# Keithley_2000_SCAN_Panasonic_V1_0.net
KiCad netlist of a schematic drawn in EasyEDA Pro
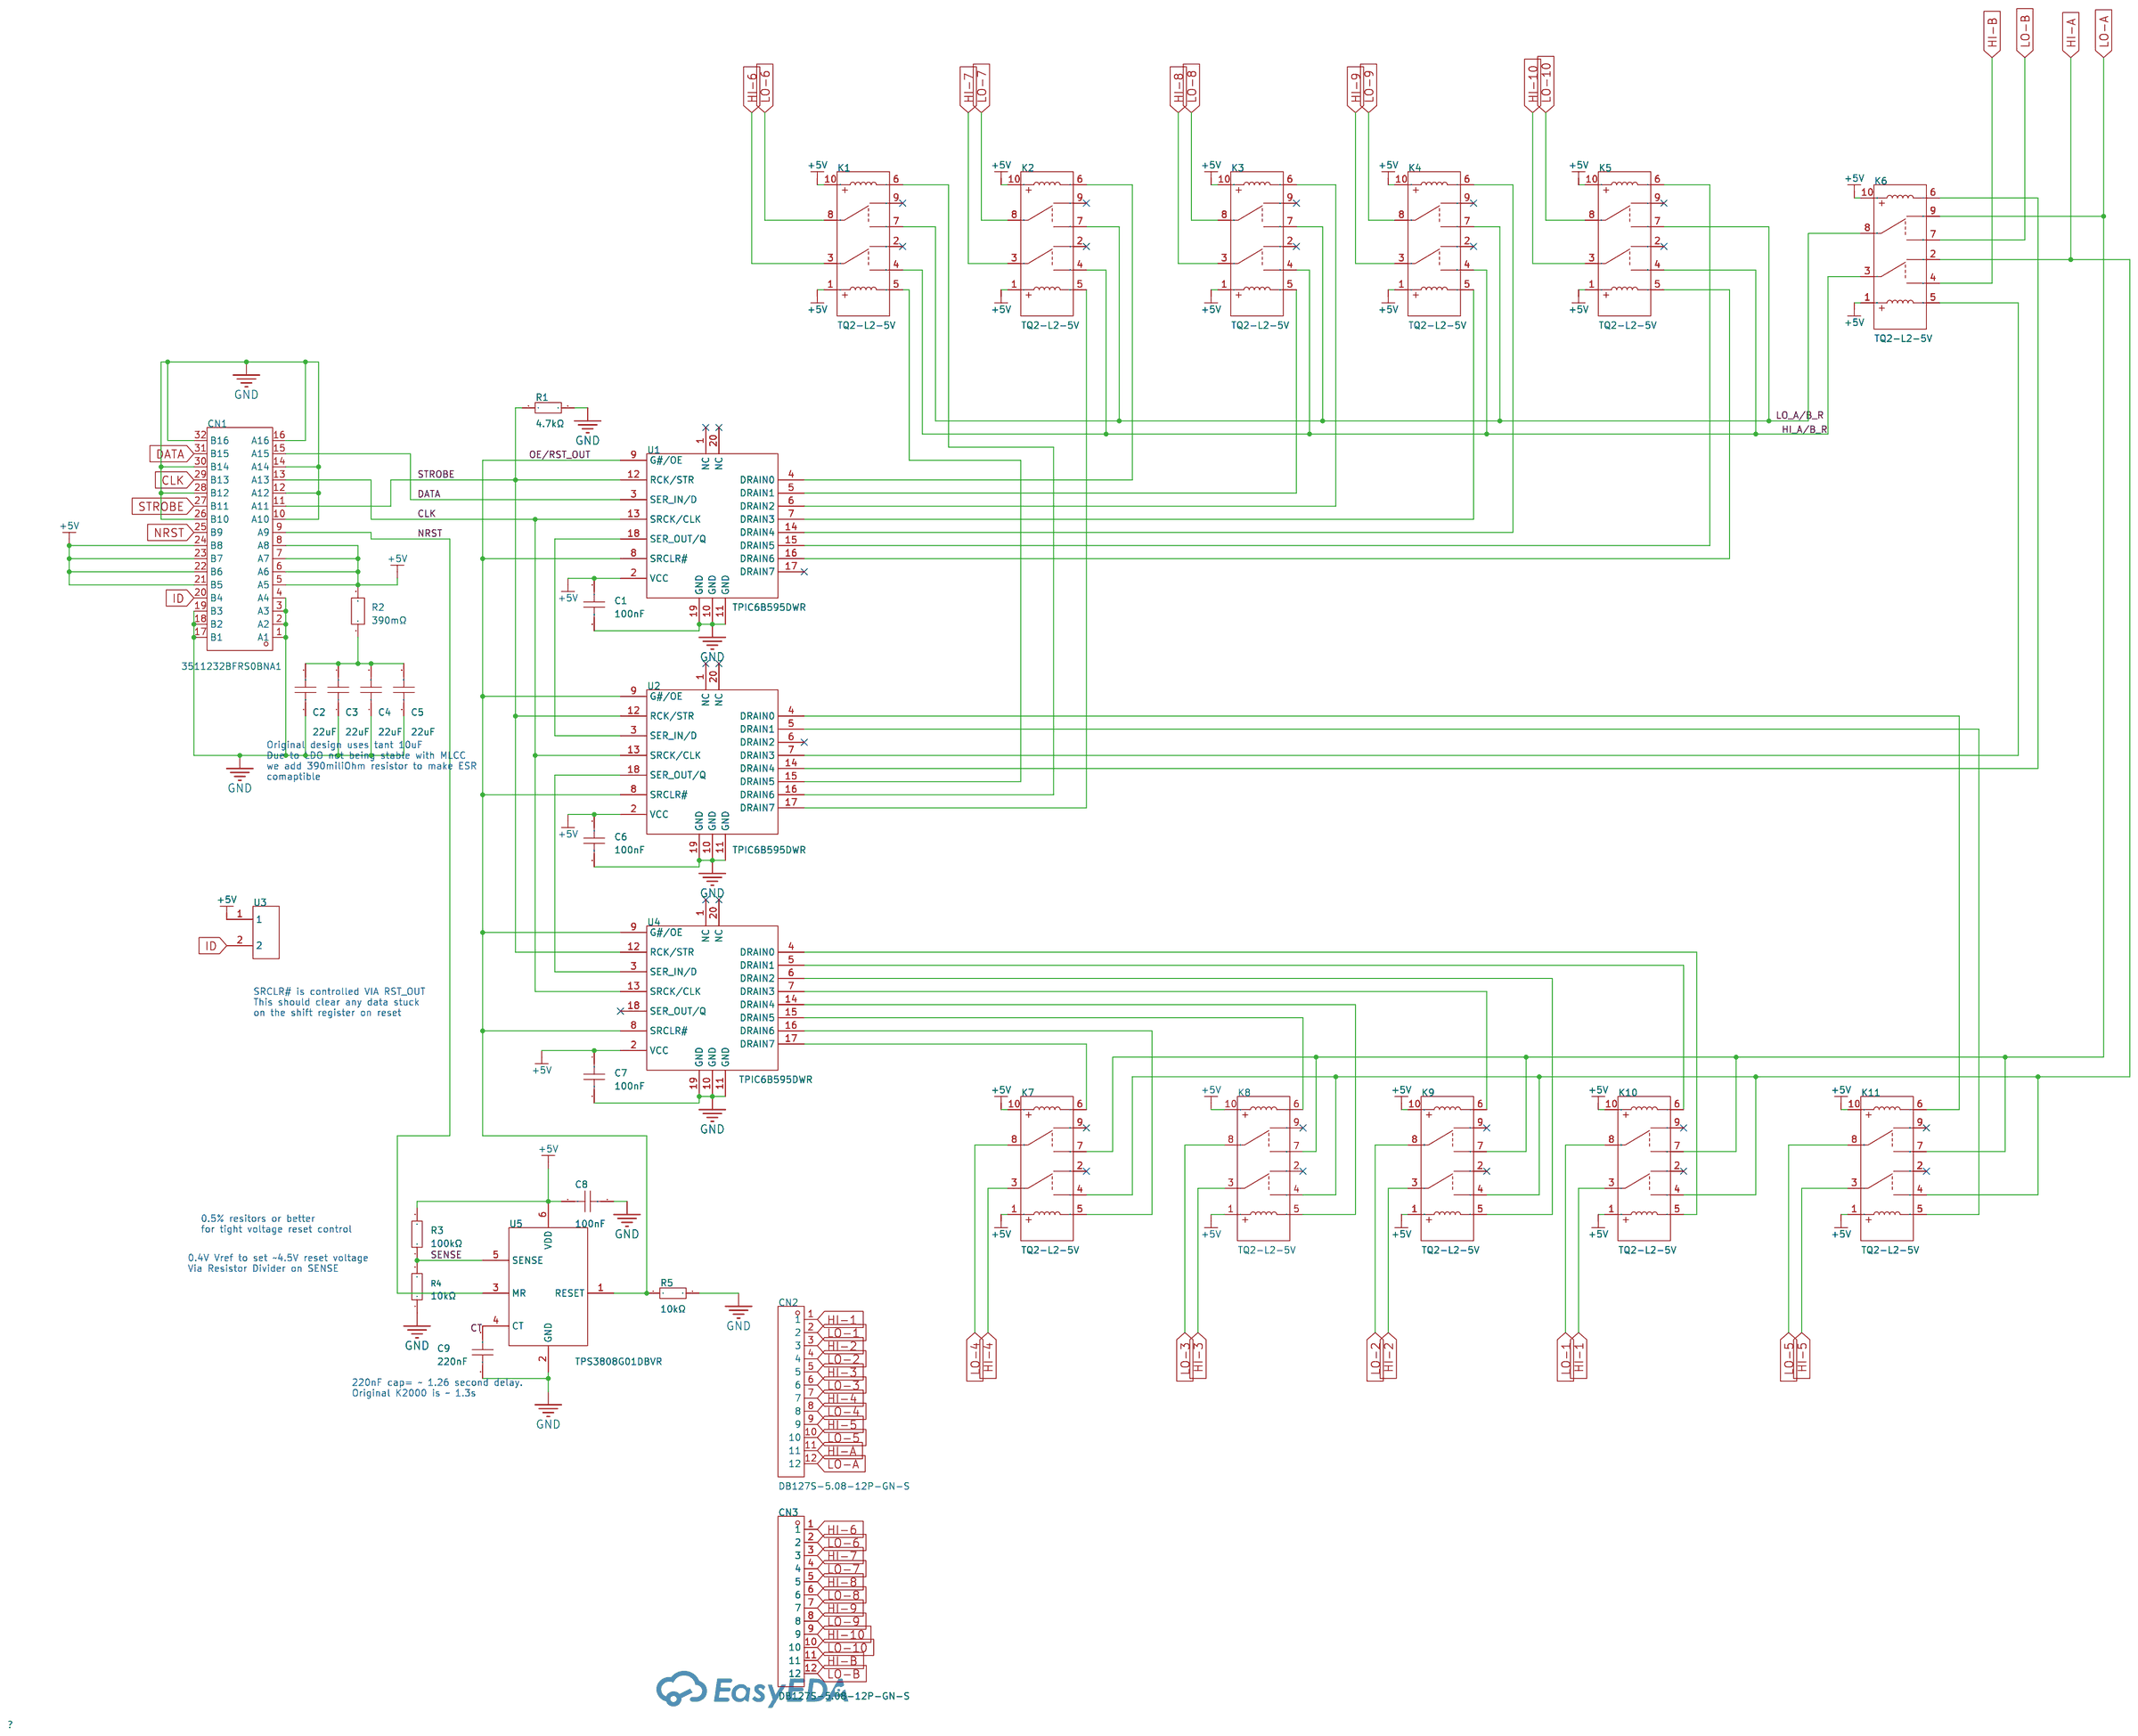
[diagram p0: schematic sheet]

(export (version "E")
  (design (tool "Eeschema 10.0.6"))
  (components
    (comp (ref "C1")
      (value "100nF")
      (description "Capacitance:100nF Tolerance:±10% Tolerance:±10% Voltage Rating:50V Temperature Coefficient:X7R")
      (fields
        (field (name "Manufacturer Part") "CL10B104KB8NNNC")
        (field (name "Manufacturer") "SAMSUNG(三星)")
      )
      (libsource (lib "easyedapro") (part "CAP"))
    )
    (comp (ref "C2")
      (value "22uF")
      (footprint "easyedapro:C0805")
      (description "Capacitance:22uF Tolerance:±20% Tolerance:±20% Voltage Rating:25V Temperature Coefficient:X5R")
      (fields
        (field (name "Manufacturer Part") "CL21A226MAYNNNE")
        (field (name "Manufacturer") "SAMSUNG(三星)")
      )
      (libsource (lib "easyedapro") (part "CL21A226MAYNNNE"))
    )
    (comp (ref "C3")
      (value "22uF")
      (footprint "easyedapro:C0805")
      (description "Capacitance:22uF Tolerance:±20% Tolerance:±20% Voltage Rating:25V Temperature Coefficient:X5R")
      (fields
        (field (name "Manufacturer Part") "CL21A226MAYNNNE")
        (field (name "Manufacturer") "SAMSUNG(三星)")
      )
      (libsource (lib "easyedapro") (part "CL21A226MAYNNNE"))
    )
    (comp (ref "C4")
      (value "22uF")
      (footprint "easyedapro:C0805")
      (description "Capacitance:22uF Tolerance:±20% Tolerance:±20% Voltage Rating:25V Temperature Coefficient:X5R")
      (fields
        (field (name "Manufacturer Part") "CL21A226MAYNNNE")
        (field (name "Manufacturer") "SAMSUNG(三星)")
      )
      (libsource (lib "easyedapro") (part "CL21A226MAYNNNE"))
    )
    (comp (ref "C5")
      (value "22uF")
      (footprint "easyedapro:C0805")
      (description "Capacitance:22uF Tolerance:±20% Tolerance:±20% Voltage Rating:25V Temperature Coefficient:X5R")
      (fields
        (field (name "Manufacturer Part") "CL21A226MAYNNNE")
        (field (name "Manufacturer") "SAMSUNG(三星)")
      )
      (libsource (lib "easyedapro") (part "CL21A226MAYNNNE"))
    )
    (comp (ref "C6")
      (value "100nF")
      (description "Capacitance:100nF Tolerance:±10% Tolerance:±10% Voltage Rating:50V Temperature Coefficient:X7R")
      (fields
        (field (name "Manufacturer Part") "CL10B104KB8NNNC")
        (field (name "Manufacturer") "SAMSUNG(三星)")
      )
      (libsource (lib "easyedapro") (part "CAP"))
    )
    (comp (ref "C7")
      (value "100nF")
      (description "Capacitance:100nF Tolerance:±10% Tolerance:±10% Voltage Rating:50V Temperature Coefficient:X7R")
      (fields
        (field (name "Manufacturer Part") "CL10B104KB8NNNC")
        (field (name "Manufacturer") "SAMSUNG(三星)")
      )
      (libsource (lib "easyedapro") (part "CAP"))
    )
    (comp (ref "C8")
      (value "100nF")
      (description "Capacitance:100nF Tolerance:±10% Tolerance:±10% Voltage Rating:50V Temperature Coefficient:X7R")
      (fields
        (field (name "Manufacturer Part") "CL10B104KB8NNNC")
        (field (name "Manufacturer") "SAMSUNG(三星)")
      )
      (libsource (lib "easyedapro") (part "CAP"))
    )
    (comp (ref "C9")
      (value "220nF")
      (description "Capacitance:220nF Tolerance:±10% Tolerance:±10% Voltage Rating:25V Temperature Coefficient:X7R")
      (fields
        (field (name "Manufacturer Part") "CL10B224KA8NNNC")
        (field (name "Manufacturer") "SAMSUNG(三星)")
      )
      (libsource (lib "easyedapro") (part "CAP"))
    )
    (comp (ref "CN1")
      (value "3511232BFRS0BNA1")
      (footprint "easyedapro:CONN-TH_3511232BFRS0BNA1")
      (fields (field (name "Manufacturer") "JILN(锦凌)"))
      (libsource (lib "easyedapro") (part "3511232BFRS0BNA1"))
    )
    (comp (ref "CN2")
      (value "DB127S-5.08-12P-GN-S")
      (footprint "easyedapro:CONN-TH_12P-P5.08_DB127S-5.08-12P-GN-S")
      (fields (field (name "Manufacturer") "DORABO(地博电气)"))
      (libsource (lib "easyedapro") (part "DB127S-5.08-12P-GN-S"))
    )
    (comp (ref "CN3")
      (value "DB127S-5.08-12P-GN-S")
      (footprint "easyedapro:CONN-TH_12P-P5.08_DB127S-5.08-12P-GN-S")
      (fields (field (name "Manufacturer") "DORABO(地博电气)"))
      (libsource (lib "easyedapro") (part "DB127S-5.08-12P-GN-S"))
    )
    (comp (ref "K1")
      (value "TQ2-L2-5V")
      (footprint "easyedapro:RELAY-TH_TQ2-L2-XXV")
      (fields (field (name "Manufacturer") "PANASONIC(松下)"))
      (libsource (lib "easyedapro") (part "TQ2-L2-5V"))
    )
    (comp (ref "K2")
      (value "TQ2-L2-5V")
      (footprint "easyedapro:RELAY-TH_TQ2-L2-XXV")
      (fields (field (name "Manufacturer") "PANASONIC(松下)"))
      (libsource (lib "easyedapro") (part "TQ2-L2-5V"))
    )
    (comp (ref "K3")
      (value "TQ2-L2-5V")
      (footprint "easyedapro:RELAY-TH_TQ2-L2-XXV")
      (fields (field (name "Manufacturer") "PANASONIC(松下)"))
      (libsource (lib "easyedapro") (part "TQ2-L2-5V"))
    )
    (comp (ref "K4")
      (value "TQ2-L2-5V")
      (footprint "easyedapro:RELAY-TH_TQ2-L2-XXV")
      (fields (field (name "Manufacturer") "PANASONIC(松下)"))
      (libsource (lib "easyedapro") (part "TQ2-L2-5V"))
    )
    (comp (ref "K5")
      (value "TQ2-L2-5V")
      (footprint "easyedapro:RELAY-TH_TQ2-L2-XXV")
      (fields (field (name "Manufacturer") "PANASONIC(松下)"))
      (libsource (lib "easyedapro") (part "TQ2-L2-5V"))
    )
    (comp (ref "K6")
      (value "TQ2-L2-5V")
      (footprint "easyedapro:RELAY-TH_TQ2-L2-XXV")
      (fields (field (name "Manufacturer") "PANASONIC(松下)"))
      (libsource (lib "easyedapro") (part "TQ2-L2-5V"))
    )
    (comp (ref "K7")
      (value "TQ2-L2-5V")
      (footprint "easyedapro:RELAY-TH_TQ2-L2-XXV")
      (fields (field (name "Manufacturer") "PANASONIC(松下)"))
      (libsource (lib "easyedapro") (part "TQ2-L2-5V"))
    )
    (comp (ref "K8")
      (value "TQ2-L2-5V")
      (footprint "easyedapro:RELAY-TH_TQ2-L2-XXV")
      (fields (field (name "Manufacturer") "PANASONIC(松下)"))
      (libsource (lib "easyedapro") (part "TQ2-L2-5V"))
    )
    (comp (ref "K9")
      (value "TQ2-L2-5V")
      (footprint "easyedapro:RELAY-TH_TQ2-L2-XXV")
      (fields (field (name "Manufacturer") "PANASONIC(松下)"))
      (libsource (lib "easyedapro") (part "TQ2-L2-5V"))
    )
    (comp (ref "K10")
      (value "TQ2-L2-5V")
      (footprint "easyedapro:RELAY-TH_TQ2-L2-XXV")
      (fields (field (name "Manufacturer") "PANASONIC(松下)"))
      (libsource (lib "easyedapro") (part "TQ2-L2-5V"))
    )
    (comp (ref "K11")
      (value "TQ2-L2-5V")
      (footprint "easyedapro:RELAY-TH_TQ2-L2-XXV")
      (fields (field (name "Manufacturer") "PANASONIC(松下)"))
      (libsource (lib "easyedapro") (part "TQ2-L2-5V"))
    )
    (comp (ref "R1")
      (value "4.7kΩ")
      (fields (field (name "Manufacturer Part") "RC0603FR-074K7L") (field (name "Manufacturer") "YAGEO(国巨)"))
      (libsource (lib "easyedapro") (part "Res"))
    )
    (comp (ref "R2")
      (value "390mΩ")
      (footprint "easyedapro:R1206")
      (fields (field (name "Manufacturer Part") "FRL1206FR390TS") (field (name "Manufacturer") "FOJAN(富捷)"))
      (libsource (lib "easyedapro") (part "FRL1206FR390TS"))
    )
    (comp (ref "R3")
      (value "100kΩ")
      (footprint "easyedapro:R0603")
      (fields (field (name "Manufacturer Part") "AR03DTCX1003") (field (name "Manufacturer") "Viking(光颉)"))
      (libsource (lib "easyedapro") (part "AR03DTCX1003"))
    )
    (comp (ref "R4")
      (value "10kΩ")
      (footprint "easyedapro:R0603")
      (fields
        (field (name "Manufacturer Part") "0603WAD1002T5E")
        (field (name "Manufacturer") "UNI-ROYAL(厚声)")
      )
      (libsource (lib "easyedapro") (part "0603WAD1002T5E"))
    )
    (comp (ref "R5")
      (value "10kΩ")
      (fields (field (name "Manufacturer Part") "RC0603FR-0710KL") (field (name "Manufacturer") "YAGEO(国巨)"))
      (libsource (lib "easyedapro") (part "Res"))
    )
    (comp (ref "U1")
      (value "TPIC6B595DWR")
      (footprint "easyedapro:SOIC-20_L13.0-W7.6-P1.27-LS10.3-BL")
      (fields (field (name "Manufacturer") "TI(德州仪器)"))
      (libsource (lib "easyedapro") (part "TPIC6B595DWR"))
    )
    (comp (ref "U2")
      (value "TPIC6B595DWR")
      (footprint "easyedapro:SOIC-20_L13.0-W7.6-P1.27-LS10.3-BL")
      (fields (field (name "Manufacturer") "TI(德州仪器)"))
      (libsource (lib "easyedapro") (part "TPIC6B595DWR"))
    )
    (comp (ref "U3")
      (value "~")
      (footprint "easyedapro:Solder Jumper New")
      (libsource (lib "easyedapro") (part "Solder Jumper New"))
    )
    (comp (ref "U4")
      (value "TPIC6B595DWR")
      (footprint "easyedapro:SOIC-20_L13.0-W7.6-P1.27-LS10.3-BL")
      (fields (field (name "Manufacturer") "TI(德州仪器)"))
      (libsource (lib "easyedapro") (part "TPIC6B595DWR"))
    )
    (comp (ref "U5")
      (value "TPS3808G01DBVR")
      (footprint "easyedapro:SOT-23-6_L2.9-W1.6-P0.95-LS2.8-BR")
      (fields (field (name "Manufacturer") "TI(德州仪器)"))
      (libsource (lib "easyedapro") (part "TPS3808G01DBVR"))
    )
  )
  (nets
    (net (code "1") (name "+5V") (class "Default")
      (node (ref "C1") (pin "1") (pinfunction "1_1") (pintype "input"))
      (node (ref "C6") (pin "1") (pinfunction "1_1") (pintype "input"))
      (node (ref "C7") (pin "1") (pinfunction "1_1") (pintype "input"))
      (node (ref "C8") (pin "2") (pinfunction "2_2") (pintype "input"))
      (node (ref "CN1") (pin "21") (pinfunction "B5_21") (pintype "unspecified"))
      (node (ref "CN1") (pin "22") (pinfunction "B6_22") (pintype "unspecified"))
      (node (ref "CN1") (pin "23") (pinfunction "B7_23") (pintype "unspecified"))
      (node (ref "CN1") (pin "24") (pinfunction "B8_24") (pintype "unspecified"))
      (node (ref "CN1") (pin "5") (pinfunction "A5_5") (pintype "unspecified"))
      (node (ref "CN1") (pin "6") (pinfunction "A6_6") (pintype "unspecified"))
      (node (ref "CN1") (pin "7") (pinfunction "A7_7") (pintype "unspecified"))
      (node (ref "CN1") (pin "8") (pinfunction "A8_8") (pintype "unspecified"))
      (node (ref "K1") (pin "1") (pinfunction "1_1") (pintype "unspecified"))
      (node (ref "K1") (pin "10") (pinfunction "6_10") (pintype "unspecified"))
      (node (ref "K10") (pin "1") (pinfunction "1_1") (pintype "unspecified"))
      (node (ref "K10") (pin "10") (pinfunction "6_10") (pintype "unspecified"))
      (node (ref "K11") (pin "1") (pinfunction "1_1") (pintype "unspecified"))
      (node (ref "K11") (pin "10") (pinfunction "6_10") (pintype "unspecified"))
      (node (ref "K2") (pin "1") (pinfunction "1_1") (pintype "unspecified"))
      (node (ref "K2") (pin "10") (pinfunction "6_10") (pintype "unspecified"))
      (node (ref "K3") (pin "1") (pinfunction "1_1") (pintype "unspecified"))
      (node (ref "K3") (pin "10") (pinfunction "6_10") (pintype "unspecified"))
      (node (ref "K4") (pin "1") (pinfunction "1_1") (pintype "unspecified"))
      (node (ref "K4") (pin "10") (pinfunction "6_10") (pintype "unspecified"))
      (node (ref "K5") (pin "1") (pinfunction "1_1") (pintype "unspecified"))
      (node (ref "K5") (pin "10") (pinfunction "6_10") (pintype "unspecified"))
      (node (ref "K6") (pin "1") (pinfunction "1_1") (pintype "unspecified"))
      (node (ref "K6") (pin "10") (pinfunction "6_10") (pintype "unspecified"))
      (node (ref "K7") (pin "1") (pinfunction "1_1") (pintype "unspecified"))
      (node (ref "K7") (pin "10") (pinfunction "6_10") (pintype "unspecified"))
      (node (ref "K8") (pin "1") (pinfunction "1_1") (pintype "unspecified"))
      (node (ref "K8") (pin "10") (pinfunction "6_10") (pintype "unspecified"))
      (node (ref "K9") (pin "1") (pinfunction "1_1") (pintype "unspecified"))
      (node (ref "K9") (pin "10") (pinfunction "6_10") (pintype "unspecified"))
      (node (ref "R2") (pin "2") (pinfunction "2_2") (pintype "unspecified"))
      (node (ref "R3") (pin "2") (pinfunction "2_2") (pintype "unspecified"))
      (node (ref "U1") (pin "2") (pinfunction "VCC_2") (pintype "unspecified"))
      (node (ref "U2") (pin "2") (pinfunction "VCC_2") (pintype "unspecified"))
      (node (ref "U3") (pin "1") (pinfunction "1_1") (pintype "input"))
      (node (ref "U4") (pin "2") (pinfunction "VCC_2") (pintype "unspecified"))
      (node (ref "U5") (pin "6") (pinfunction "VDD_6") (pintype "unspecified"))
    )
    (net (code "2") (name "/CT") (class "Default")
      (node (ref "C9") (pin "1") (pinfunction "1_1") (pintype "input"))
      (node (ref "U5") (pin "4") (pinfunction "CT_4") (pintype "unspecified"))
    )
    (net (code "3") (name "/HI_A{slash}B_R") (class "Default")
      (node (ref "K1") (pin "4") (pinfunction "5_4") (pintype "unspecified"))
      (node (ref "K2") (pin "4") (pinfunction "5_4") (pintype "unspecified"))
      (node (ref "K3") (pin "4") (pinfunction "5_4") (pintype "unspecified"))
      (node (ref "K4") (pin "4") (pinfunction "5_4") (pintype "unspecified"))
      (node (ref "K5") (pin "4") (pinfunction "5_4") (pintype "unspecified"))
      (node (ref "K6") (pin "3") (pinfunction "4_3") (pintype "unspecified"))
    )
    (net (code "4") (name "/LO_A{slash}B_R") (class "Default")
      (node (ref "K1") (pin "7") (pinfunction "8_7") (pintype "unspecified"))
      (node (ref "K2") (pin "7") (pinfunction "8_7") (pintype "unspecified"))
      (node (ref "K3") (pin "7") (pinfunction "8_7") (pintype "unspecified"))
      (node (ref "K4") (pin "7") (pinfunction "8_7") (pintype "unspecified"))
      (node (ref "K5") (pin "7") (pinfunction "8_7") (pintype "unspecified"))
      (node (ref "K6") (pin "8") (pinfunction "9_8") (pintype "unspecified"))
    )
    (net (code "5") (name "/OE{slash}RST_OUT") (class "Default")
      (node (ref "R5") (pin "1") (pinfunction "1_1") (pintype "input"))
      (node (ref "U1") (pin "8") (pinfunction "SRCLR#_8") (pintype "unspecified"))
      (node (ref "U1") (pin "9") (pinfunction "G#/OE_9") (pintype "unspecified"))
      (node (ref "U2") (pin "8") (pinfunction "SRCLR#_8") (pintype "unspecified"))
      (node (ref "U2") (pin "9") (pinfunction "G#/OE_9") (pintype "unspecified"))
      (node (ref "U4") (pin "8") (pinfunction "SRCLR#_8") (pintype "unspecified"))
      (node (ref "U4") (pin "9") (pinfunction "G#/OE_9") (pintype "unspecified"))
      (node (ref "U5") (pin "1") (pinfunction "RESET_1") (pintype "unspecified"))
    )
    (net (code "6") (name "/SENSE") (class "Default")
      (node (ref "R3") (pin "1") (pinfunction "1_1") (pintype "unspecified"))
      (node (ref "R4") (pin "2") (pinfunction "2_2") (pintype "input"))
      (node (ref "U5") (pin "5") (pinfunction "SENSE_5") (pintype "unspecified"))
    )
    (net (code "7") (name "CLK") (class "Default")
      (node (ref "CN1") (pin "13") (pinfunction "A13_13") (pintype "unspecified"))
      (node (ref "CN1") (pin "29") (pinfunction "B13_29") (pintype "unspecified"))
      (node (ref "U1") (pin "13") (pinfunction "SRCK/CLK_13") (pintype "unspecified"))
      (node (ref "U2") (pin "13") (pinfunction "SRCK/CLK_13") (pintype "unspecified"))
      (node (ref "U4") (pin "13") (pinfunction "SRCK/CLK_13") (pintype "unspecified"))
    )
    (net (code "8") (name "DATA") (class "Default")
      (node (ref "CN1") (pin "15") (pinfunction "A15_15") (pintype "unspecified"))
      (node (ref "CN1") (pin "31") (pinfunction "B15_31") (pintype "unspecified"))
      (node (ref "U1") (pin "3") (pinfunction "SER_IN/D_3") (pintype "unspecified"))
    )
    (net (code "9") (name "GND") (class "Default")
      (node (ref "C1") (pin "2") (pinfunction "2_2") (pintype "input"))
      (node (ref "C2") (pin "1") (pinfunction "1_1") (pintype "unspecified"))
      (node (ref "C3") (pin "1") (pinfunction "1_1") (pintype "unspecified"))
      (node (ref "C4") (pin "1") (pinfunction "1_1") (pintype "unspecified"))
      (node (ref "C5") (pin "1") (pinfunction "1_1") (pintype "unspecified"))
      (node (ref "C6") (pin "2") (pinfunction "2_2") (pintype "input"))
      (node (ref "C7") (pin "2") (pinfunction "2_2") (pintype "input"))
      (node (ref "C8") (pin "1") (pinfunction "1_1") (pintype "input"))
      (node (ref "C9") (pin "2") (pinfunction "2_2") (pintype "input"))
      (node (ref "CN1") (pin "1") (pinfunction "A1_1") (pintype "unspecified"))
      (node (ref "CN1") (pin "10") (pinfunction "A10_10") (pintype "unspecified"))
      (node (ref "CN1") (pin "12") (pinfunction "A12_12") (pintype "unspecified"))
      (node (ref "CN1") (pin "14") (pinfunction "A14_14") (pintype "unspecified"))
      (node (ref "CN1") (pin "16") (pinfunction "A16_16") (pintype "unspecified"))
      (node (ref "CN1") (pin "17") (pinfunction "B1_17") (pintype "unspecified"))
      (node (ref "CN1") (pin "18") (pinfunction "B2_18") (pintype "unspecified"))
      (node (ref "CN1") (pin "19") (pinfunction "B3_19") (pintype "unspecified"))
      (node (ref "CN1") (pin "2") (pinfunction "A2_2") (pintype "unspecified"))
      (node (ref "CN1") (pin "26") (pinfunction "B10_26") (pintype "unspecified"))
      (node (ref "CN1") (pin "28") (pinfunction "B12_28") (pintype "unspecified"))
      (node (ref "CN1") (pin "3") (pinfunction "A3_3") (pintype "unspecified"))
      (node (ref "CN1") (pin "30") (pinfunction "B14_30") (pintype "unspecified"))
      (node (ref "CN1") (pin "32") (pinfunction "B16_32") (pintype "unspecified"))
      (node (ref "CN1") (pin "4") (pinfunction "A4_4") (pintype "unspecified"))
      (node (ref "R1") (pin "2") (pinfunction "2_2") (pintype "input"))
      (node (ref "R4") (pin "1") (pinfunction "1_1") (pintype "input"))
      (node (ref "R5") (pin "2") (pinfunction "2_2") (pintype "input"))
      (node (ref "U1") (pin "10") (pinfunction "GND_10") (pintype "unspecified"))
      (node (ref "U1") (pin "11") (pinfunction "GND_11") (pintype "unspecified"))
      (node (ref "U1") (pin "19") (pinfunction "GND_19") (pintype "unspecified"))
      (node (ref "U2") (pin "10") (pinfunction "GND_10") (pintype "unspecified"))
      (node (ref "U2") (pin "11") (pinfunction "GND_11") (pintype "unspecified"))
      (node (ref "U2") (pin "19") (pinfunction "GND_19") (pintype "unspecified"))
      (node (ref "U4") (pin "10") (pinfunction "GND_10") (pintype "unspecified"))
      (node (ref "U4") (pin "11") (pinfunction "GND_11") (pintype "unspecified"))
      (node (ref "U4") (pin "19") (pinfunction "GND_19") (pintype "unspecified"))
      (node (ref "U5") (pin "2") (pinfunction "GND_2") (pintype "unspecified"))
    )
    (net (code "10") (name "HI-1") (class "Default")
      (node (ref "CN2") (pin "1") (pinfunction "1_1") (pintype "unspecified"))
      (node (ref "K10") (pin "3") (pinfunction "4_3") (pintype "unspecified"))
    )
    (net (code "11") (name "HI-2") (class "Default")
      (node (ref "CN2") (pin "3") (pinfunction "3_3") (pintype "unspecified"))
      (node (ref "K9") (pin "3") (pinfunction "4_3") (pintype "unspecified"))
    )
    (net (code "12") (name "HI-3") (class "Default")
      (node (ref "CN2") (pin "5") (pinfunction "5_5") (pintype "unspecified"))
      (node (ref "K8") (pin "3") (pinfunction "4_3") (pintype "unspecified"))
    )
    (net (code "13") (name "HI-4") (class "Default")
      (node (ref "CN2") (pin "7") (pinfunction "7_7") (pintype "unspecified"))
      (node (ref "K7") (pin "3") (pinfunction "4_3") (pintype "unspecified"))
    )
    (net (code "14") (name "HI-5") (class "Default")
      (node (ref "CN2") (pin "9") (pinfunction "9_9") (pintype "unspecified"))
      (node (ref "K11") (pin "3") (pinfunction "4_3") (pintype "unspecified"))
    )
    (net (code "15") (name "HI-6") (class "Default")
      (node (ref "CN3") (pin "1") (pinfunction "1_1") (pintype "unspecified"))
      (node (ref "K1") (pin "3") (pinfunction "4_3") (pintype "unspecified"))
    )
    (net (code "16") (name "HI-7") (class "Default")
      (node (ref "CN3") (pin "3") (pinfunction "3_3") (pintype "unspecified"))
      (node (ref "K2") (pin "3") (pinfunction "4_3") (pintype "unspecified"))
    )
    (net (code "17") (name "HI-8") (class "Default")
      (node (ref "CN3") (pin "5") (pinfunction "5_5") (pintype "unspecified"))
      (node (ref "K3") (pin "3") (pinfunction "4_3") (pintype "unspecified"))
    )
    (net (code "18") (name "HI-9") (class "Default")
      (node (ref "CN3") (pin "7") (pinfunction "7_7") (pintype "unspecified"))
      (node (ref "K4") (pin "3") (pinfunction "4_3") (pintype "unspecified"))
    )
    (net (code "19") (name "HI-10") (class "Default")
      (node (ref "CN3") (pin "9") (pinfunction "9_9") (pintype "unspecified"))
      (node (ref "K5") (pin "3") (pinfunction "4_3") (pintype "unspecified"))
    )
    (net (code "20") (name "HI-A") (class "Default")
      (node (ref "CN2") (pin "11") (pinfunction "11_11") (pintype "unspecified"))
      (node (ref "K10") (pin "4") (pinfunction "5_4") (pintype "unspecified"))
      (node (ref "K11") (pin "4") (pinfunction "5_4") (pintype "unspecified"))
      (node (ref "K6") (pin "2") (pinfunction "3_2") (pintype "unspecified"))
      (node (ref "K7") (pin "4") (pinfunction "5_4") (pintype "unspecified"))
      (node (ref "K8") (pin "4") (pinfunction "5_4") (pintype "unspecified"))
      (node (ref "K9") (pin "4") (pinfunction "5_4") (pintype "unspecified"))
    )
    (net (code "21") (name "HI-B") (class "Default")
      (node (ref "CN3") (pin "11") (pinfunction "11_11") (pintype "unspecified"))
      (node (ref "K6") (pin "4") (pinfunction "5_4") (pintype "unspecified"))
    )
    (net (code "22") (name "ID") (class "Default")
      (node (ref "CN1") (pin "20") (pinfunction "B4_20") (pintype "unspecified"))
      (node (ref "U3") (pin "2") (pinfunction "2_2") (pintype "input"))
    )
    (net (code "23") (name "LO-1") (class "Default")
      (node (ref "CN2") (pin "2") (pinfunction "2_2") (pintype "unspecified"))
      (node (ref "K10") (pin "8") (pinfunction "9_8") (pintype "unspecified"))
    )
    (net (code "24") (name "LO-2") (class "Default")
      (node (ref "CN2") (pin "4") (pinfunction "4_4") (pintype "unspecified"))
      (node (ref "K9") (pin "8") (pinfunction "9_8") (pintype "unspecified"))
    )
    (net (code "25") (name "LO-3") (class "Default")
      (node (ref "CN2") (pin "6") (pinfunction "6_6") (pintype "unspecified"))
      (node (ref "K8") (pin "8") (pinfunction "9_8") (pintype "unspecified"))
    )
    (net (code "26") (name "LO-4") (class "Default")
      (node (ref "CN2") (pin "8") (pinfunction "8_8") (pintype "unspecified"))
      (node (ref "K7") (pin "8") (pinfunction "9_8") (pintype "unspecified"))
    )
    (net (code "27") (name "LO-5") (class "Default")
      (node (ref "CN2") (pin "10") (pinfunction "10_10") (pintype "unspecified"))
      (node (ref "K11") (pin "8") (pinfunction "9_8") (pintype "unspecified"))
    )
    (net (code "28") (name "LO-6") (class "Default")
      (node (ref "CN3") (pin "2") (pinfunction "2_2") (pintype "unspecified"))
      (node (ref "K1") (pin "8") (pinfunction "9_8") (pintype "unspecified"))
    )
    (net (code "29") (name "LO-7") (class "Default")
      (node (ref "CN3") (pin "4") (pinfunction "4_4") (pintype "unspecified"))
      (node (ref "K2") (pin "8") (pinfunction "9_8") (pintype "unspecified"))
    )
    (net (code "30") (name "LO-8") (class "Default")
      (node (ref "CN3") (pin "6") (pinfunction "6_6") (pintype "unspecified"))
      (node (ref "K3") (pin "8") (pinfunction "9_8") (pintype "unspecified"))
    )
    (net (code "31") (name "LO-9") (class "Default")
      (node (ref "CN3") (pin "8") (pinfunction "8_8") (pintype "unspecified"))
      (node (ref "K4") (pin "8") (pinfunction "9_8") (pintype "unspecified"))
    )
    (net (code "32") (name "LO-10") (class "Default")
      (node (ref "CN3") (pin "10") (pinfunction "10_10") (pintype "unspecified"))
      (node (ref "K5") (pin "8") (pinfunction "9_8") (pintype "unspecified"))
    )
    (net (code "33") (name "LO-A") (class "Default")
      (node (ref "CN2") (pin "12") (pinfunction "12_12") (pintype "unspecified"))
      (node (ref "K10") (pin "7") (pinfunction "8_7") (pintype "unspecified"))
      (node (ref "K11") (pin "7") (pinfunction "8_7") (pintype "unspecified"))
      (node (ref "K6") (pin "9") (pinfunction "10_9") (pintype "unspecified"))
      (node (ref "K7") (pin "7") (pinfunction "8_7") (pintype "unspecified"))
      (node (ref "K8") (pin "7") (pinfunction "8_7") (pintype "unspecified"))
      (node (ref "K9") (pin "7") (pinfunction "8_7") (pintype "unspecified"))
    )
    (net (code "34") (name "LO-B") (class "Default")
      (node (ref "CN3") (pin "12") (pinfunction "12_12") (pintype "unspecified"))
      (node (ref "K6") (pin "7") (pinfunction "8_7") (pintype "unspecified"))
    )
    (net (code "35") (name "NRST") (class "Default")
      (node (ref "CN1") (pin "25") (pinfunction "B9_25") (pintype "unspecified"))
      (node (ref "CN1") (pin "9") (pinfunction "A9_9") (pintype "unspecified"))
      (node (ref "U5") (pin "3") (pinfunction "MR_3") (pintype "unspecified"))
    )
    (net (code "36") (name "Net-(C2-Pad2)") (class "Default")
      (node (ref "C2") (pin "2") (pinfunction "2_2") (pintype "unspecified"))
      (node (ref "C3") (pin "2") (pinfunction "2_2") (pintype "unspecified"))
      (node (ref "C4") (pin "2") (pinfunction "2_2") (pintype "unspecified"))
      (node (ref "C5") (pin "2") (pinfunction "2_2") (pintype "unspecified"))
      (node (ref "R2") (pin "1") (pinfunction "1_1") (pintype "unspecified"))
    )
    (net (code "37") (name "Net-(K1-7)") (class "Default")
      (node (ref "K1") (pin "6") (pinfunction "7_6") (pintype "unspecified"))
      (node (ref "U2") (pin "16") (pinfunction "DRAIN6_16") (pintype "unspecified"))
    )
    (net (code "38") (name "Net-(K1-12)") (class "Default")
      (node (ref "K1") (pin "5") (pinfunction "12_5") (pintype "unspecified"))
      (node (ref "U2") (pin "15") (pinfunction "DRAIN5_15") (pintype "unspecified"))
    )
    (net (code "39") (name "Net-(K2-7)") (class "Default")
      (node (ref "K2") (pin "6") (pinfunction "7_6") (pintype "unspecified"))
      (node (ref "U1") (pin "4") (pinfunction "DRAIN0_4") (pintype "unspecified"))
    )
    (net (code "40") (name "Net-(K2-12)") (class "Default")
      (node (ref "K2") (pin "5") (pinfunction "12_5") (pintype "unspecified"))
      (node (ref "U2") (pin "17") (pinfunction "DRAIN7_17") (pintype "unspecified"))
    )
    (net (code "41") (name "Net-(K3-7)") (class "Default")
      (node (ref "K3") (pin "6") (pinfunction "7_6") (pintype "unspecified"))
      (node (ref "U1") (pin "6") (pinfunction "DRAIN2_6") (pintype "unspecified"))
    )
    (net (code "42") (name "Net-(K3-12)") (class "Default")
      (node (ref "K3") (pin "5") (pinfunction "12_5") (pintype "unspecified"))
      (node (ref "U1") (pin "5") (pinfunction "DRAIN1_5") (pintype "unspecified"))
    )
    (net (code "43") (name "Net-(K4-7)") (class "Default")
      (node (ref "K4") (pin "6") (pinfunction "7_6") (pintype "unspecified"))
      (node (ref "U1") (pin "14") (pinfunction "DRAIN4_14") (pintype "unspecified"))
    )
    (net (code "44") (name "Net-(K4-12)") (class "Default")
      (node (ref "K4") (pin "5") (pinfunction "12_5") (pintype "unspecified"))
      (node (ref "U1") (pin "7") (pinfunction "DRAIN3_7") (pintype "unspecified"))
    )
    (net (code "45") (name "Net-(K5-7)") (class "Default")
      (node (ref "K5") (pin "6") (pinfunction "7_6") (pintype "unspecified"))
      (node (ref "U1") (pin "15") (pinfunction "DRAIN5_15") (pintype "unspecified"))
    )
    (net (code "46") (name "Net-(K5-12)") (class "Default")
      (node (ref "K5") (pin "5") (pinfunction "12_5") (pintype "unspecified"))
      (node (ref "U1") (pin "16") (pinfunction "DRAIN6_16") (pintype "unspecified"))
    )
    (net (code "47") (name "Net-(K6-7)") (class "Default")
      (node (ref "K6") (pin "6") (pinfunction "7_6") (pintype "unspecified"))
      (node (ref "U2") (pin "14") (pinfunction "DRAIN4_14") (pintype "unspecified"))
    )
    (net (code "48") (name "Net-(K6-12)") (class "Default")
      (node (ref "K6") (pin "5") (pinfunction "12_5") (pintype "unspecified"))
      (node (ref "U2") (pin "7") (pinfunction "DRAIN3_7") (pintype "unspecified"))
    )
    (net (code "49") (name "Net-(K7-7)") (class "Default")
      (node (ref "K7") (pin "6") (pinfunction "7_6") (pintype "unspecified"))
      (node (ref "U4") (pin "17") (pinfunction "DRAIN7_17") (pintype "unspecified"))
    )
    (net (code "50") (name "Net-(K7-12)") (class "Default")
      (node (ref "K7") (pin "5") (pinfunction "12_5") (pintype "unspecified"))
      (node (ref "U4") (pin "16") (pinfunction "DRAIN6_16") (pintype "unspecified"))
    )
    (net (code "51") (name "Net-(K8-7)") (class "Default")
      (node (ref "K8") (pin "6") (pinfunction "7_6") (pintype "unspecified"))
      (node (ref "U4") (pin "15") (pinfunction "DRAIN5_15") (pintype "unspecified"))
    )
    (net (code "52") (name "Net-(K8-12)") (class "Default")
      (node (ref "K8") (pin "5") (pinfunction "12_5") (pintype "unspecified"))
      (node (ref "U4") (pin "14") (pinfunction "DRAIN4_14") (pintype "unspecified"))
    )
    (net (code "53") (name "Net-(K9-7)") (class "Default")
      (node (ref "K9") (pin "6") (pinfunction "7_6") (pintype "unspecified"))
      (node (ref "U4") (pin "7") (pinfunction "DRAIN3_7") (pintype "unspecified"))
    )
    (net (code "54") (name "Net-(K9-12)") (class "Default")
      (node (ref "K9") (pin "5") (pinfunction "12_5") (pintype "unspecified"))
      (node (ref "U4") (pin "6") (pinfunction "DRAIN2_6") (pintype "unspecified"))
    )
    (net (code "55") (name "Net-(K10-7)") (class "Default")
      (node (ref "K10") (pin "6") (pinfunction "7_6") (pintype "unspecified"))
      (node (ref "U4") (pin "5") (pinfunction "DRAIN1_5") (pintype "unspecified"))
    )
    (net (code "56") (name "Net-(K10-12)") (class "Default")
      (node (ref "K10") (pin "5") (pinfunction "12_5") (pintype "unspecified"))
      (node (ref "U4") (pin "4") (pinfunction "DRAIN0_4") (pintype "unspecified"))
    )
    (net (code "57") (name "Net-(K11-7)") (class "Default")
      (node (ref "K11") (pin "6") (pinfunction "7_6") (pintype "unspecified"))
      (node (ref "U2") (pin "4") (pinfunction "DRAIN0_4") (pintype "unspecified"))
    )
    (net (code "58") (name "Net-(K11-12)") (class "Default")
      (node (ref "K11") (pin "5") (pinfunction "12_5") (pintype "unspecified"))
      (node (ref "U2") (pin "5") (pinfunction "DRAIN1_5") (pintype "unspecified"))
    )
    (net (code "59") (name "Net-(U1-SER_OUT{slash}Q)") (class "Default")
      (node (ref "U1") (pin "18") (pinfunction "SER_OUT/Q_18") (pintype "unspecified"))
      (node (ref "U2") (pin "3") (pinfunction "SER_IN/D_3") (pintype "unspecified"))
    )
    (net (code "60") (name "Net-(U2-SER_OUT{slash}Q)") (class "Default")
      (node (ref "U2") (pin "18") (pinfunction "SER_OUT/Q_18") (pintype "unspecified"))
      (node (ref "U4") (pin "3") (pinfunction "SER_IN/D_3") (pintype "unspecified"))
    )
    (net (code "61") (name "STROBE") (class "Default")
      (node (ref "CN1") (pin "11") (pinfunction "A11_11") (pintype "unspecified"))
      (node (ref "CN1") (pin "27") (pinfunction "B11_27") (pintype "unspecified"))
      (node (ref "R1") (pin "1") (pinfunction "1_1") (pintype "input"))
      (node (ref "U1") (pin "12") (pinfunction "RCK/STR_12") (pintype "unspecified"))
      (node (ref "U2") (pin "12") (pinfunction "RCK/STR_12") (pintype "unspecified"))
      (node (ref "U4") (pin "12") (pinfunction "RCK/STR_12") (pintype "unspecified"))
    )
    (net (code "62") (name "unconnected-(K1-3-Pad2)") (class "Default")
      (node (ref "K1") (pin "2") (pinfunction "3_2") (pintype "unspecified+no_connect"))
    )
    (net (code "63") (name "unconnected-(K1-10-Pad9)") (class "Default")
      (node (ref "K1") (pin "9") (pinfunction "10_9") (pintype "unspecified+no_connect"))
    )
    (net (code "64") (name "unconnected-(K2-3-Pad2)") (class "Default")
      (node (ref "K2") (pin "2") (pinfunction "3_2") (pintype "unspecified+no_connect"))
    )
    (net (code "65") (name "unconnected-(K2-10-Pad9)") (class "Default")
      (node (ref "K2") (pin "9") (pinfunction "10_9") (pintype "unspecified+no_connect"))
    )
    (net (code "66") (name "unconnected-(K3-3-Pad2)") (class "Default")
      (node (ref "K3") (pin "2") (pinfunction "3_2") (pintype "unspecified+no_connect"))
    )
    (net (code "67") (name "unconnected-(K3-10-Pad9)") (class "Default")
      (node (ref "K3") (pin "9") (pinfunction "10_9") (pintype "unspecified+no_connect"))
    )
    (net (code "68") (name "unconnected-(K4-3-Pad2)") (class "Default")
      (node (ref "K4") (pin "2") (pinfunction "3_2") (pintype "unspecified+no_connect"))
    )
    (net (code "69") (name "unconnected-(K4-10-Pad9)") (class "Default")
      (node (ref "K4") (pin "9") (pinfunction "10_9") (pintype "unspecified+no_connect"))
    )
    (net (code "70") (name "unconnected-(K5-3-Pad2)") (class "Default")
      (node (ref "K5") (pin "2") (pinfunction "3_2") (pintype "unspecified+no_connect"))
    )
    (net (code "71") (name "unconnected-(K5-10-Pad9)") (class "Default")
      (node (ref "K5") (pin "9") (pinfunction "10_9") (pintype "unspecified+no_connect"))
    )
    (net (code "72") (name "unconnected-(K7-3-Pad2)") (class "Default")
      (node (ref "K7") (pin "2") (pinfunction "3_2") (pintype "unspecified+no_connect"))
    )
    (net (code "73") (name "unconnected-(K7-10-Pad9)") (class "Default")
      (node (ref "K7") (pin "9") (pinfunction "10_9") (pintype "unspecified+no_connect"))
    )
    (net (code "74") (name "unconnected-(K8-3-Pad2)") (class "Default")
      (node (ref "K8") (pin "2") (pinfunction "3_2") (pintype "unspecified+no_connect"))
    )
    (net (code "75") (name "unconnected-(K8-10-Pad9)") (class "Default")
      (node (ref "K8") (pin "9") (pinfunction "10_9") (pintype "unspecified+no_connect"))
    )
    (net (code "76") (name "unconnected-(K9-3-Pad2)") (class "Default")
      (node (ref "K9") (pin "2") (pinfunction "3_2") (pintype "unspecified+no_connect"))
    )
    (net (code "77") (name "unconnected-(K9-10-Pad9)") (class "Default")
      (node (ref "K9") (pin "9") (pinfunction "10_9") (pintype "unspecified+no_connect"))
    )
    (net (code "78") (name "unconnected-(K10-3-Pad2)") (class "Default")
      (node (ref "K10") (pin "2") (pinfunction "3_2") (pintype "unspecified+no_connect"))
    )
    (net (code "79") (name "unconnected-(K10-10-Pad9)") (class "Default")
      (node (ref "K10") (pin "9") (pinfunction "10_9") (pintype "unspecified+no_connect"))
    )
    (net (code "80") (name "unconnected-(K11-3-Pad2)") (class "Default")
      (node (ref "K11") (pin "2") (pinfunction "3_2") (pintype "unspecified+no_connect"))
    )
    (net (code "81") (name "unconnected-(K11-10-Pad9)") (class "Default")
      (node (ref "K11") (pin "9") (pinfunction "10_9") (pintype "unspecified+no_connect"))
    )
    (net (code "82") (name "unconnected-(U1-DRAIN7-Pad17)") (class "Default")
      (node (ref "U1") (pin "17") (pinfunction "DRAIN7_17") (pintype "unspecified+no_connect"))
    )
    (net (code "83") (name "unconnected-(U1-NC-Pad1)") (class "Default")
      (node (ref "U1") (pin "1") (pinfunction "NC_1") (pintype "unspecified+no_connect"))
    )
    (net (code "84") (name "unconnected-(U1-NC-Pad20)") (class "Default")
      (node (ref "U1") (pin "20") (pinfunction "NC_20") (pintype "unspecified+no_connect"))
    )
    (net (code "85") (name "unconnected-(U2-DRAIN2-Pad6)") (class "Default")
      (node (ref "U2") (pin "6") (pinfunction "DRAIN2_6") (pintype "unspecified+no_connect"))
    )
    (net (code "86") (name "unconnected-(U2-NC-Pad1)") (class "Default")
      (node (ref "U2") (pin "1") (pinfunction "NC_1") (pintype "unspecified+no_connect"))
    )
    (net (code "87") (name "unconnected-(U2-NC-Pad20)") (class "Default")
      (node (ref "U2") (pin "20") (pinfunction "NC_20") (pintype "unspecified+no_connect"))
    )
    (net (code "88") (name "unconnected-(U4-NC-Pad1)") (class "Default")
      (node (ref "U4") (pin "1") (pinfunction "NC_1") (pintype "unspecified+no_connect"))
    )
    (net (code "89") (name "unconnected-(U4-NC-Pad20)") (class "Default")
      (node (ref "U4") (pin "20") (pinfunction "NC_20") (pintype "unspecified+no_connect"))
    )
    (net (code "90") (name "unconnected-(U4-SER_OUT{slash}Q-Pad18)") (class "Default")
      (node (ref "U4") (pin "18") (pinfunction "SER_OUT/Q_18") (pintype "unspecified+no_connect"))
    )
  )
)
